# SchematicWeatherStationModule.net
KiCad netlist of a schematic drawn in EAGLE
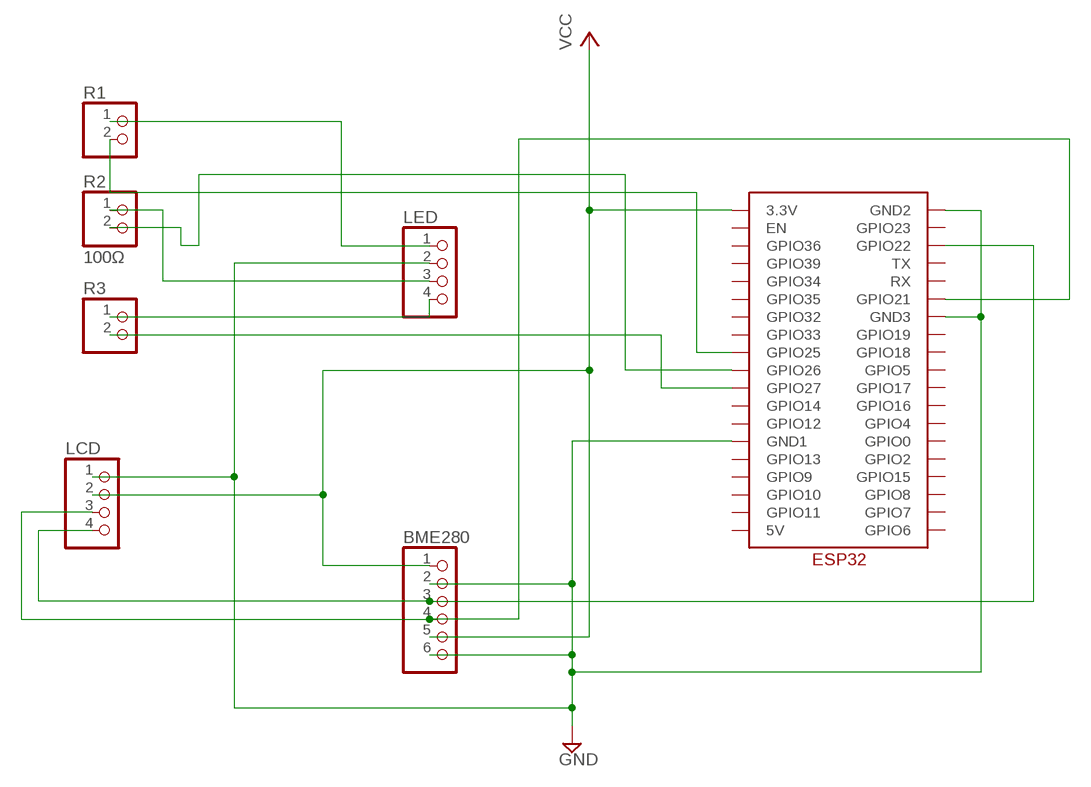
[diagram p0: schematic, sheet 1]

(export (version "E")
  (design (tool "Eeschema 10.0.6"))
  (components
    (comp (ref "BME280")
      (value "PINHD-1X6/90")
      (footprint "eagle-import:1X06_90")
      (libsource (lib "eagle-import") (part "PINHD-1X6/90"))
    )
    (comp (ref "LCD")
      (value "PINHD-1X4/90")
      (footprint "eagle-import:1X04_90")
      (libsource (lib "eagle-import") (part "PINHD-1X4/90"))
    )
    (comp (ref "LED")
      (value "PINHD-1X4")
      (footprint "eagle-import:1X04")
      (libsource (lib "eagle-import") (part "PINHD-1X4"))
    )
    (comp (ref "R1")
      (value "PINHD-1X2")
      (footprint "eagle-import:1X02")
      (libsource (lib "eagle-import") (part "PINHD-1X2"))
    )
    (comp (ref "R2")
      (value "100Ω")
      (footprint "eagle-import:1X02")
      (libsource (lib "eagle-import") (part "PINHD-1X2"))
    )
    (comp (ref "R3")
      (value "PINHD-1X2")
      (footprint "eagle-import:1X02")
      (libsource (lib "eagle-import") (part "PINHD-1X2"))
    )
    (comp (ref "U$1")
      (value "ESP32")
      (footprint "eagle-import:ESP32")
      (libsource (lib "eagle-import") (part "ESP32"))
    )
  )
  (nets
    (net (code "1") (name "GND") (class "Default")
      (node (ref "BME280") (pin "2") (pinfunction "2_2") (pintype "passive"))
      (node (ref "BME280") (pin "6") (pinfunction "6_6") (pintype "passive"))
      (node (ref "LCD") (pin "1") (pinfunction "1_1") (pintype "passive"))
      (node (ref "LED") (pin "2") (pinfunction "2_2") (pintype "passive"))
      (node (ref "U$1") (pin "GND1") (pinfunction "GND1_GND1") (pintype "bidirectional"))
      (node (ref "U$1") (pin "GND2") (pinfunction "GND2_GND2") (pintype "bidirectional"))
      (node (ref "U$1") (pin "GND3") (pinfunction "GND3_GND3") (pintype "bidirectional"))
    )
    (net (code "2") (name "Net-(BME280-Pad3)") (class "Default")
      (node (ref "BME280") (pin "3") (pinfunction "3_3") (pintype "passive"))
      (node (ref "LCD") (pin "4") (pinfunction "4_4") (pintype "passive"))
      (node (ref "U$1") (pin "GPIO22") (pinfunction "GPIO22_GPIO22") (pintype "bidirectional"))
    )
    (net (code "3") (name "Net-(BME280-Pad4)") (class "Default")
      (node (ref "BME280") (pin "4") (pinfunction "4_4") (pintype "passive"))
      (node (ref "LCD") (pin "3") (pinfunction "3_3") (pintype "passive"))
      (node (ref "U$1") (pin "GPIO21") (pinfunction "GPIO21_GPIO21") (pintype "bidirectional"))
    )
    (net (code "4") (name "Net-(LED-Pad1)") (class "Default")
      (node (ref "LED") (pin "1") (pinfunction "1_1") (pintype "passive"))
      (node (ref "R1") (pin "1") (pinfunction "1_1") (pintype "passive"))
    )
    (net (code "5") (name "Net-(LED-Pad3)") (class "Default")
      (node (ref "LED") (pin "3") (pinfunction "3_3") (pintype "passive"))
      (node (ref "R2") (pin "1") (pinfunction "1_1") (pintype "passive"))
    )
    (net (code "6") (name "Net-(LED-Pad4)") (class "Default")
      (node (ref "LED") (pin "4") (pinfunction "4_4") (pintype "passive"))
      (node (ref "R3") (pin "1") (pinfunction "1_1") (pintype "passive"))
    )
    (net (code "7") (name "Net-(R1-Pad2)") (class "Default")
      (node (ref "R1") (pin "2") (pinfunction "2_2") (pintype "passive"))
      (node (ref "U$1") (pin "GPIO25") (pinfunction "GPIO25_GPIO25") (pintype "bidirectional"))
    )
    (net (code "8") (name "Net-(R2-Pad2)") (class "Default")
      (node (ref "R2") (pin "2") (pinfunction "2_2") (pintype "passive"))
      (node (ref "U$1") (pin "GPIO26") (pinfunction "GPIO26_GPIO26") (pintype "bidirectional"))
    )
    (net (code "9") (name "Net-(R3-Pad2)") (class "Default")
      (node (ref "R3") (pin "2") (pinfunction "2_2") (pintype "passive"))
      (node (ref "U$1") (pin "GPIO27") (pinfunction "GPIO27_GPIO27") (pintype "bidirectional"))
    )
    (net (code "10") (name "VCC") (class "Default")
      (node (ref "BME280") (pin "1") (pinfunction "1_1") (pintype "passive"))
      (node (ref "BME280") (pin "5") (pinfunction "5_5") (pintype "passive"))
      (node (ref "LCD") (pin "2") (pinfunction "2_2") (pintype "passive"))
      (node (ref "U$1") (pin "3.3V") (pinfunction "3.3V_3.3V") (pintype "bidirectional"))
    )
    (net (code "11") (name "unconnected-(U$1-Pad5V)") (class "Default")
      (node (ref "U$1") (pin "5V") (pinfunction "5V_5V") (pintype "bidirectional"))
    )
    (net (code "12") (name "unconnected-(U$1-PadEN)") (class "Default")
      (node (ref "U$1") (pin "EN") (pinfunction "EN_EN") (pintype "bidirectional"))
    )
    (net (code "13") (name "unconnected-(U$1-PadGPIO0)") (class "Default")
      (node (ref "U$1") (pin "GPIO0") (pinfunction "GPIO0_GPIO0") (pintype "bidirectional"))
    )
    (net (code "14") (name "unconnected-(U$1-PadGPIO2)") (class "Default")
      (node (ref "U$1") (pin "GPIO2") (pinfunction "GPIO2_GPIO2") (pintype "bidirectional"))
    )
    (net (code "15") (name "unconnected-(U$1-PadGPIO4)") (class "Default")
      (node (ref "U$1") (pin "GPIO4") (pinfunction "GPIO4_GPIO4") (pintype "bidirectional"))
    )
    (net (code "16") (name "unconnected-(U$1-PadGPIO5)") (class "Default")
      (node (ref "U$1") (pin "GPIO5") (pinfunction "GPIO5_GPIO5") (pintype "bidirectional"))
    )
    (net (code "17") (name "unconnected-(U$1-PadGPIO6)") (class "Default")
      (node (ref "U$1") (pin "GPIO6") (pinfunction "GPIO6_GPIO6") (pintype "bidirectional"))
    )
    (net (code "18") (name "unconnected-(U$1-PadGPIO7)") (class "Default")
      (node (ref "U$1") (pin "GPIO7") (pinfunction "GPIO7_GPIO7") (pintype "bidirectional"))
    )
    (net (code "19") (name "unconnected-(U$1-PadGPIO8)") (class "Default")
      (node (ref "U$1") (pin "GPIO8") (pinfunction "GPIO8_GPIO8") (pintype "bidirectional"))
    )
    (net (code "20") (name "unconnected-(U$1-PadGPIO9)") (class "Default")
      (node (ref "U$1") (pin "GPIO9") (pinfunction "GPIO9_GPIO9") (pintype "bidirectional"))
    )
    (net (code "21") (name "unconnected-(U$1-PadGPIO10)") (class "Default")
      (node (ref "U$1") (pin "GPIO10") (pinfunction "GPIO10_GPIO10") (pintype "bidirectional"))
    )
    (net (code "22") (name "unconnected-(U$1-PadGPIO11)") (class "Default")
      (node (ref "U$1") (pin "GPIO11") (pinfunction "GPIO11_GPIO11") (pintype "bidirectional"))
    )
    (net (code "23") (name "unconnected-(U$1-PadGPIO12)") (class "Default")
      (node (ref "U$1") (pin "GPIO12") (pinfunction "GPIO12_GPIO12") (pintype "bidirectional"))
    )
    (net (code "24") (name "unconnected-(U$1-PadGPIO13)") (class "Default")
      (node (ref "U$1") (pin "GPIO13") (pinfunction "GPIO13_GPIO13") (pintype "bidirectional"))
    )
    (net (code "25") (name "unconnected-(U$1-PadGPIO14)") (class "Default")
      (node (ref "U$1") (pin "GPIO14") (pinfunction "GPIO14_GPIO14") (pintype "bidirectional"))
    )
    (net (code "26") (name "unconnected-(U$1-PadGPIO15)") (class "Default")
      (node (ref "U$1") (pin "GPIO15") (pinfunction "GPIO15_GPIO15") (pintype "bidirectional"))
    )
    (net (code "27") (name "unconnected-(U$1-PadGPIO16)") (class "Default")
      (node (ref "U$1") (pin "GPIO16") (pinfunction "GPIO16_GPIO16") (pintype "bidirectional"))
    )
    (net (code "28") (name "unconnected-(U$1-PadGPIO17)") (class "Default")
      (node (ref "U$1") (pin "GPIO17") (pinfunction "GPIO17_GPIO17") (pintype "bidirectional"))
    )
    (net (code "29") (name "unconnected-(U$1-PadGPIO18)") (class "Default")
      (node (ref "U$1") (pin "GPIO18") (pinfunction "GPIO18_GPIO18") (pintype "bidirectional"))
    )
    (net (code "30") (name "unconnected-(U$1-PadGPIO19)") (class "Default")
      (node (ref "U$1") (pin "GPIO19") (pinfunction "GPIO19_GPIO19") (pintype "bidirectional"))
    )
    (net (code "31") (name "unconnected-(U$1-PadGPIO23)") (class "Default")
      (node (ref "U$1") (pin "GPIO23") (pinfunction "GPIO23_GPIO23") (pintype "bidirectional"))
    )
    (net (code "32") (name "unconnected-(U$1-PadGPIO32)") (class "Default")
      (node (ref "U$1") (pin "GPIO32") (pinfunction "GPIO32_GPIO32") (pintype "bidirectional"))
    )
    (net (code "33") (name "unconnected-(U$1-PadGPIO33)") (class "Default")
      (node (ref "U$1") (pin "GPIO33") (pinfunction "GPIO33_GPIO33") (pintype "bidirectional"))
    )
    (net (code "34") (name "unconnected-(U$1-PadGPIO34)") (class "Default")
      (node (ref "U$1") (pin "GPIO34") (pinfunction "GPIO34_GPIO34") (pintype "bidirectional"))
    )
    (net (code "35") (name "unconnected-(U$1-PadGPIO35)") (class "Default")
      (node (ref "U$1") (pin "GPIO35") (pinfunction "GPIO35_GPIO35") (pintype "bidirectional"))
    )
    (net (code "36") (name "unconnected-(U$1-PadGPIO36)") (class "Default")
      (node (ref "U$1") (pin "GPIO36") (pinfunction "GPIO36_GPIO36") (pintype "bidirectional"))
    )
    (net (code "37") (name "unconnected-(U$1-PadGPIO39)") (class "Default")
      (node (ref "U$1") (pin "GPIO39") (pinfunction "GPIO39_GPIO39") (pintype "bidirectional"))
    )
    (net (code "38") (name "unconnected-(U$1-PadRX)") (class "Default")
      (node (ref "U$1") (pin "RX") (pinfunction "RX_RX") (pintype "bidirectional"))
    )
    (net (code "39") (name "unconnected-(U$1-PadTX)") (class "Default")
      (node (ref "U$1") (pin "TX") (pinfunction "TX_TX") (pintype "bidirectional"))
    )
  )
)
